# CanSatSecundaria.net
KiCad netlist of a schematic drawn in EAGLE
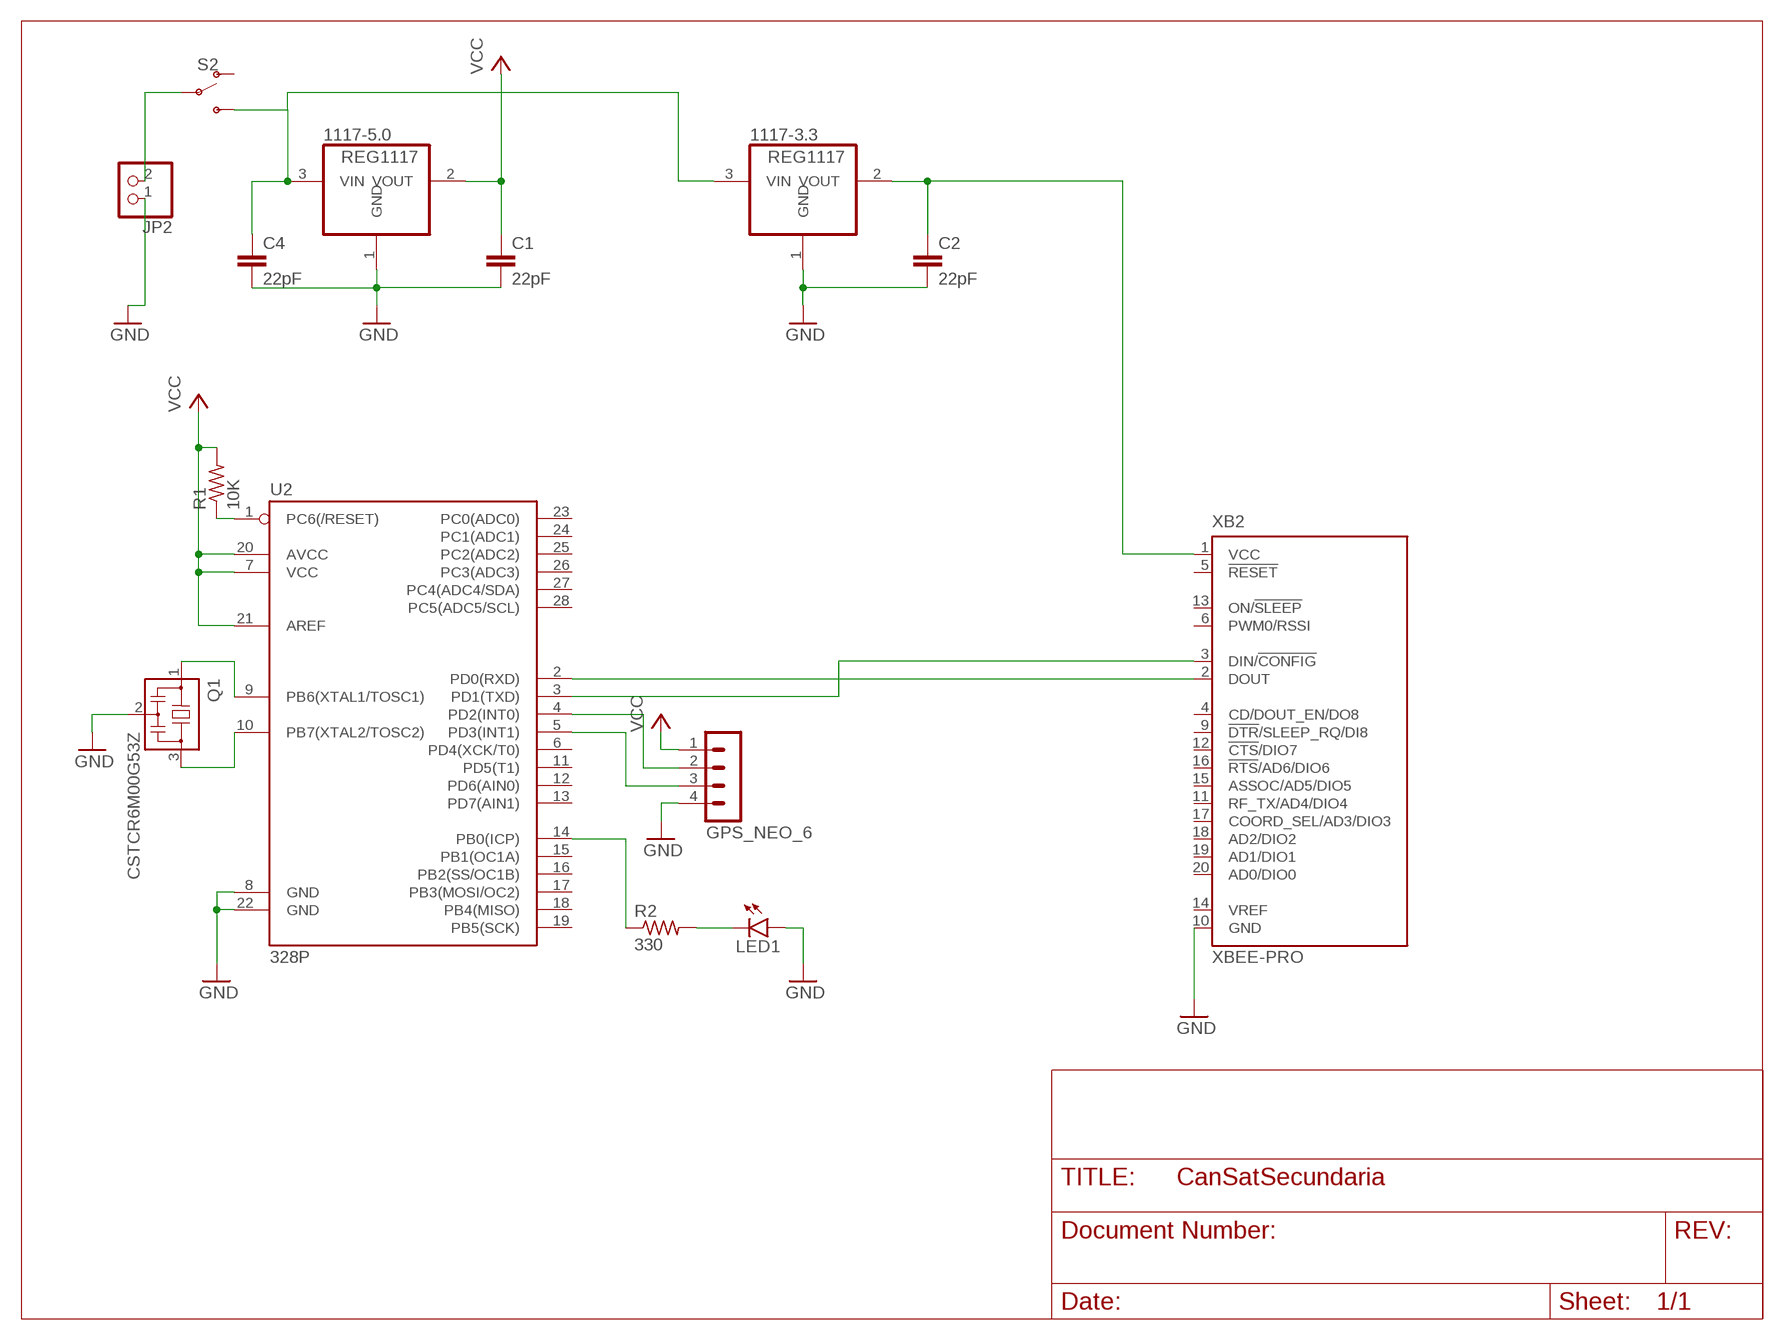
[diagram p0: schematic, sheet 1]

(export (version "E")
  (design (tool "Eeschema 10.0.6"))
  (components
    (comp (ref "1117-3.3")
      (value "REG1117")
      (footprint "eagle-import:SOT223")
      (libsource (lib "eagle-import") (part "REG1117"))
    )
    (comp (ref "1117-5.0")
      (value "REG1117")
      (footprint "eagle-import:SOT223")
      (libsource (lib "eagle-import") (part "REG1117"))
    )
    (comp (ref "C1")
      (value "22pF")
      (footprint "eagle-import:C1206")
      (libsource (lib "eagle-import") (part "C-EUC1206"))
    )
    (comp (ref "C2")
      (value "22pF")
      (footprint "eagle-import:C1206")
      (libsource (lib "eagle-import") (part "C-EUC1206"))
    )
    (comp (ref "C4")
      (value "22pF")
      (footprint "eagle-import:C1206")
      (libsource (lib "eagle-import") (part "C-EUC1206"))
    )
    (comp (ref "GPS_NEO_6")
      (value "MA04-1")
      (footprint "eagle-import:MA04-1")
      (libsource (lib "eagle-import") (part "MA04-1"))
    )
    (comp (ref "JP2")
      (value "PINHD-1X2/90")
      (footprint "eagle-import:1X02_90")
      (libsource (lib "eagle-import") (part "PINHD-1X2/90"))
    )
    (comp (ref "LED1")
      (value "LEDSMT1206")
      (footprint "eagle-import:1206")
      (libsource (lib "eagle-import") (part "LEDSMT1206"))
    )
    (comp (ref "Q1")
      (value "CSTCR6M00G53Z")
      (footprint "eagle-import:CSTCR6M")
      (fields (field (name "MPN") "CSTCR6M00G53-R0"))
      (libsource (lib "eagle-import") (part "CSTCR6M00G53Z"))
    )
    (comp (ref "R1")
      (value "10K")
      (footprint "eagle-import:M1206")
      (libsource (lib "eagle-import") (part "R-US_M1206"))
    )
    (comp (ref "R2")
      (value "330")
      (footprint "eagle-import:R1206")
      (libsource (lib "eagle-import") (part "R-US_R1206"))
    )
    (comp (ref "S2")
      (value "SWITCH-SPDT-SMD-RIGHT-ANGLE")
      (footprint "eagle-import:SWITCH_SPST_SMD_A")
      (libsource (lib "eagle-import") (part "SWITCH-SPDT-SMD-RIGHT-ANGLE"))
    )
    (comp (ref "U2")
      (value "328P")
      (footprint "eagle-import:DIP28")
      (libsource (lib "eagle-import") (part "ATMEGA328P_PDIP"))
    )
    (comp (ref "XB2")
      (value "XBEE-PRO")
      (footprint "eagle-import:XBEE-PRO")
      (fields (field (name "MPN") "XBP24-AWI-001"))
      (libsource (lib "eagle-import") (part "XBEE-PRO"))
    )
  )
  (nets
    (net (code "1") (name "GND") (class "Default")
      (node (ref "1117-3.3") (pin "1") (pinfunction "GND_1") (pintype "power_in"))
      (node (ref "1117-5.0") (pin "1") (pinfunction "GND_1") (pintype "power_in"))
      (node (ref "C1") (pin "2") (pinfunction "2_2") (pintype "passive"))
      (node (ref "C2") (pin "2") (pinfunction "2_2") (pintype "passive"))
      (node (ref "C4") (pin "2") (pinfunction "2_2") (pintype "passive"))
      (node (ref "GPS_NEO_6") (pin "4") (pinfunction "4_4") (pintype "passive"))
      (node (ref "JP2") (pin "1") (pinfunction "1_1") (pintype "passive"))
      (node (ref "LED1") (pin "A") (pinfunction "A_A") (pintype "passive"))
      (node (ref "Q1") (pin "2") (pinfunction "2_2") (pintype "passive"))
      (node (ref "U2") (pin "22") (pinfunction "GND_22") (pintype "bidirectional"))
      (node (ref "U2") (pin "8") (pinfunction "GND_8") (pintype "bidirectional"))
      (node (ref "XB2") (pin "10") (pinfunction "GND_10") (pintype "power_in"))
    )
    (net (code "2") (name "Net-(1117-3.3-VIN)") (class "Default")
      (node (ref "1117-3.3") (pin "3") (pinfunction "VIN_3") (pintype "input"))
      (node (ref "1117-5.0") (pin "3") (pinfunction "VIN_3") (pintype "input"))
      (node (ref "C4") (pin "1") (pinfunction "1_1") (pintype "passive"))
      (node (ref "S2") (pin "3") (pinfunction "S_3") (pintype "passive"))
    )
    (net (code "3") (name "Net-(1117-3.3-VOUT)") (class "Default")
      (node (ref "1117-3.3") (pin "2") (pinfunction "VOUT_2") (pintype "output"))
      (node (ref "C2") (pin "1") (pinfunction "1_1") (pintype "passive"))
      (node (ref "XB2") (pin "1") (pinfunction "VCC_1") (pintype "power_in"))
    )
    (net (code "4") (name "Net-(LED1-PadC)") (class "Default")
      (node (ref "LED1") (pin "C") (pinfunction "C_C") (pintype "passive"))
      (node (ref "R2") (pin "2") (pinfunction "2_2") (pintype "passive"))
    )
    (net (code "5") (name "Net-(S2-P)") (class "Default")
      (node (ref "JP2") (pin "2") (pinfunction "2_2") (pintype "passive"))
      (node (ref "S2") (pin "2") (pinfunction "P_2") (pintype "passive"))
    )
    (net (code "6") (name "Net-(U2-PB0(ICP))") (class "Default")
      (node (ref "R2") (pin "1") (pinfunction "1_1") (pintype "passive"))
      (node (ref "U2") (pin "14") (pinfunction "PB0(ICP)_14") (pintype "bidirectional"))
    )
    (net (code "7") (name "Net-(U2-PB6(XTAL1{slash}TOSC1))") (class "Default")
      (node (ref "Q1") (pin "1") (pinfunction "1_1") (pintype "passive"))
      (node (ref "U2") (pin "9") (pinfunction "PB6(XTAL1/TOSC1)_9") (pintype "bidirectional"))
    )
    (net (code "8") (name "Net-(U2-PB7(XTAL2{slash}TOSC2))") (class "Default")
      (node (ref "Q1") (pin "3") (pinfunction "3_3") (pintype "passive"))
      (node (ref "U2") (pin "10") (pinfunction "PB7(XTAL2/TOSC2)_10") (pintype "bidirectional"))
    )
    (net (code "9") (name "Net-(U2-PC6({slash}RESET))") (class "Default")
      (node (ref "R1") (pin "1") (pinfunction "1_1") (pintype "passive"))
      (node (ref "U2") (pin "1") (pinfunction "PC6(/RESET)_1") (pintype "bidirectional"))
    )
    (net (code "10") (name "Net-(U2-PD0(RXD))") (class "Default")
      (node (ref "U2") (pin "2") (pinfunction "PD0(RXD)_2") (pintype "bidirectional"))
      (node (ref "XB2") (pin "2") (pinfunction "DOUT_2") (pintype "output"))
    )
    (net (code "11") (name "Net-(U2-PD1(TXD))") (class "Default")
      (node (ref "U2") (pin "3") (pinfunction "PD1(TXD)_3") (pintype "bidirectional"))
      (node (ref "XB2") (pin "3") (pinfunction "DIN/~{CONFIG}_3") (pintype "input"))
    )
    (net (code "12") (name "Net-(U2-PD2(INT0))") (class "Default")
      (node (ref "GPS_NEO_6") (pin "2") (pinfunction "2_2") (pintype "passive"))
      (node (ref "U2") (pin "4") (pinfunction "PD2(INT0)_4") (pintype "bidirectional"))
    )
    (net (code "13") (name "Net-(U2-PD3(INT1))") (class "Default")
      (node (ref "GPS_NEO_6") (pin "3") (pinfunction "3_3") (pintype "passive"))
      (node (ref "U2") (pin "5") (pinfunction "PD3(INT1)_5") (pintype "bidirectional"))
    )
    (net (code "14") (name "VCC") (class "Default")
      (node (ref "1117-5.0") (pin "2") (pinfunction "VOUT_2") (pintype "output"))
      (node (ref "C1") (pin "1") (pinfunction "1_1") (pintype "passive"))
      (node (ref "GPS_NEO_6") (pin "1") (pinfunction "1_1") (pintype "passive"))
      (node (ref "R1") (pin "2") (pinfunction "2_2") (pintype "passive"))
      (node (ref "U2") (pin "20") (pinfunction "AVCC_20") (pintype "bidirectional"))
      (node (ref "U2") (pin "21") (pinfunction "AREF_21") (pintype "bidirectional"))
      (node (ref "U2") (pin "7") (pinfunction "VCC_7") (pintype "bidirectional"))
    )
    (net (code "15") (name "unconnected-(S2-O-Pad1)") (class "Default")
      (node (ref "S2") (pin "1") (pinfunction "O_1") (pintype "passive"))
    )
    (net (code "16") (name "unconnected-(U2-PB1(OC1A)-Pad15)") (class "Default")
      (node (ref "U2") (pin "15") (pinfunction "PB1(OC1A)_15") (pintype "bidirectional"))
    )
    (net (code "17") (name "unconnected-(U2-PB2(SS{slash}OC1B)-Pad16)") (class "Default")
      (node (ref "U2") (pin "16") (pinfunction "PB2(SS/OC1B)_16") (pintype "bidirectional"))
    )
    (net (code "18") (name "unconnected-(U2-PB3(MOSI{slash}OC2)-Pad17)") (class "Default")
      (node (ref "U2") (pin "17") (pinfunction "PB3(MOSI/OC2)_17") (pintype "bidirectional"))
    )
    (net (code "19") (name "unconnected-(U2-PB4(MISO)-Pad18)") (class "Default")
      (node (ref "U2") (pin "18") (pinfunction "PB4(MISO)_18") (pintype "bidirectional"))
    )
    (net (code "20") (name "unconnected-(U2-PB5(SCK)-Pad19)") (class "Default")
      (node (ref "U2") (pin "19") (pinfunction "PB5(SCK)_19") (pintype "bidirectional"))
    )
    (net (code "21") (name "unconnected-(U2-PC0(ADC0)-Pad23)") (class "Default")
      (node (ref "U2") (pin "23") (pinfunction "PC0(ADC0)_23") (pintype "bidirectional"))
    )
    (net (code "22") (name "unconnected-(U2-PC1(ADC1)-Pad24)") (class "Default")
      (node (ref "U2") (pin "24") (pinfunction "PC1(ADC1)_24") (pintype "bidirectional"))
    )
    (net (code "23") (name "unconnected-(U2-PC2(ADC2)-Pad25)") (class "Default")
      (node (ref "U2") (pin "25") (pinfunction "PC2(ADC2)_25") (pintype "bidirectional"))
    )
    (net (code "24") (name "unconnected-(U2-PC3(ADC3)-Pad26)") (class "Default")
      (node (ref "U2") (pin "26") (pinfunction "PC3(ADC3)_26") (pintype "bidirectional"))
    )
    (net (code "25") (name "unconnected-(U2-PC4(ADC4{slash}SDA)-Pad27)") (class "Default")
      (node (ref "U2") (pin "27") (pinfunction "PC4(ADC4/SDA)_27") (pintype "bidirectional"))
    )
    (net (code "26") (name "unconnected-(U2-PC5(ADC5{slash}SCL)-Pad28)") (class "Default")
      (node (ref "U2") (pin "28") (pinfunction "PC5(ADC5/SCL)_28") (pintype "bidirectional"))
    )
    (net (code "27") (name "unconnected-(U2-PD4(XCK{slash}T0)-Pad6)") (class "Default")
      (node (ref "U2") (pin "6") (pinfunction "PD4(XCK/T0)_6") (pintype "bidirectional"))
    )
    (net (code "28") (name "unconnected-(U2-PD5(T1)-Pad11)") (class "Default")
      (node (ref "U2") (pin "11") (pinfunction "PD5(T1)_11") (pintype "bidirectional"))
    )
    (net (code "29") (name "unconnected-(U2-PD6(AIN0)-Pad12)") (class "Default")
      (node (ref "U2") (pin "12") (pinfunction "PD6(AIN0)_12") (pintype "bidirectional"))
    )
    (net (code "30") (name "unconnected-(U2-PD7(AIN1)-Pad13)") (class "Default")
      (node (ref "U2") (pin "13") (pinfunction "PD7(AIN1)_13") (pintype "bidirectional"))
    )
    (net (code "31") (name "unconnected-(XB2-AD0{slash}DIO0-Pad20)") (class "Default")
      (node (ref "XB2") (pin "20") (pinfunction "AD0/DIO0_20") (pintype "bidirectional"))
    )
    (net (code "32") (name "unconnected-(XB2-AD1{slash}DIO1-Pad19)") (class "Default")
      (node (ref "XB2") (pin "19") (pinfunction "AD1/DIO1_19") (pintype "bidirectional"))
    )
    (net (code "33") (name "unconnected-(XB2-AD2{slash}DIO2-Pad18)") (class "Default")
      (node (ref "XB2") (pin "18") (pinfunction "AD2/DIO2_18") (pintype "bidirectional"))
    )
    (net (code "34") (name "unconnected-(XB2-ASSOC{slash}AD5{slash}DIO5-Pad15)") (class "Default")
      (node (ref "XB2") (pin "15") (pinfunction "ASSOC/AD5/DIO5_15") (pintype "bidirectional"))
    )
    (net (code "35") (name "unconnected-(XB2-CD{slash}DOUT_EN{slash}DO8-Pad4)") (class "Default")
      (node (ref "XB2") (pin "4") (pinfunction "CD/DOUT_EN/DO8_4") (pintype "output"))
    )
    (net (code "36") (name "unconnected-(XB2-COORD_SEL{slash}AD3{slash}DIO3-Pad17)") (class "Default")
      (node (ref "XB2") (pin "17") (pinfunction "COORD_SEL/AD3/DIO3_17") (pintype "bidirectional"))
    )
    (net (code "37") (name "unconnected-(XB2-ON{slash}~{SLEEP}-Pad13)") (class "Default")
      (node (ref "XB2") (pin "13") (pinfunction "ON/~{SLEEP}_13") (pintype "output"))
    )
    (net (code "38") (name "unconnected-(XB2-PWM0{slash}RSSI-Pad6)") (class "Default")
      (node (ref "XB2") (pin "6") (pinfunction "PWM0/RSSI_6") (pintype "output"))
    )
    (net (code "39") (name "unconnected-(XB2-RF_TX{slash}AD4{slash}DIO4-Pad11)") (class "Default")
      (node (ref "XB2") (pin "11") (pinfunction "RF_TX/AD4/DIO4_11") (pintype "bidirectional"))
    )
    (net (code "40") (name "unconnected-(XB2-VREF-Pad14)") (class "Default")
      (node (ref "XB2") (pin "14") (pinfunction "VREF_14") (pintype "input"))
    )
    (net (code "41") (name "unconnected-(XB2-~{CTS}{slash}DIO7-Pad12)") (class "Default")
      (node (ref "XB2") (pin "12") (pinfunction "~{CTS}/DIO7_12") (pintype "bidirectional"))
    )
    (net (code "42") (name "unconnected-(XB2-~{DTR}{slash}SLEEP_RQ{slash}DI8-Pad9)") (class "Default")
      (node (ref "XB2") (pin "9") (pinfunction "~{DTR}/SLEEP_RQ/DI8_9") (pintype "bidirectional"))
    )
    (net (code "43") (name "unconnected-(XB2-~{RESET}-Pad5)") (class "Default")
      (node (ref "XB2") (pin "5") (pinfunction "~{RESET}_5") (pintype "input"))
    )
    (net (code "44") (name "unconnected-(XB2-~{RTS}{slash}AD6{slash}DIO6-Pad16)") (class "Default")
      (node (ref "XB2") (pin "16") (pinfunction "~{RTS}/AD6/DIO6_16") (pintype "bidirectional"))
    )
  )
)
